# stm32f0_i2s.net
KiCad netlist of a schematic drawn in EAGLE
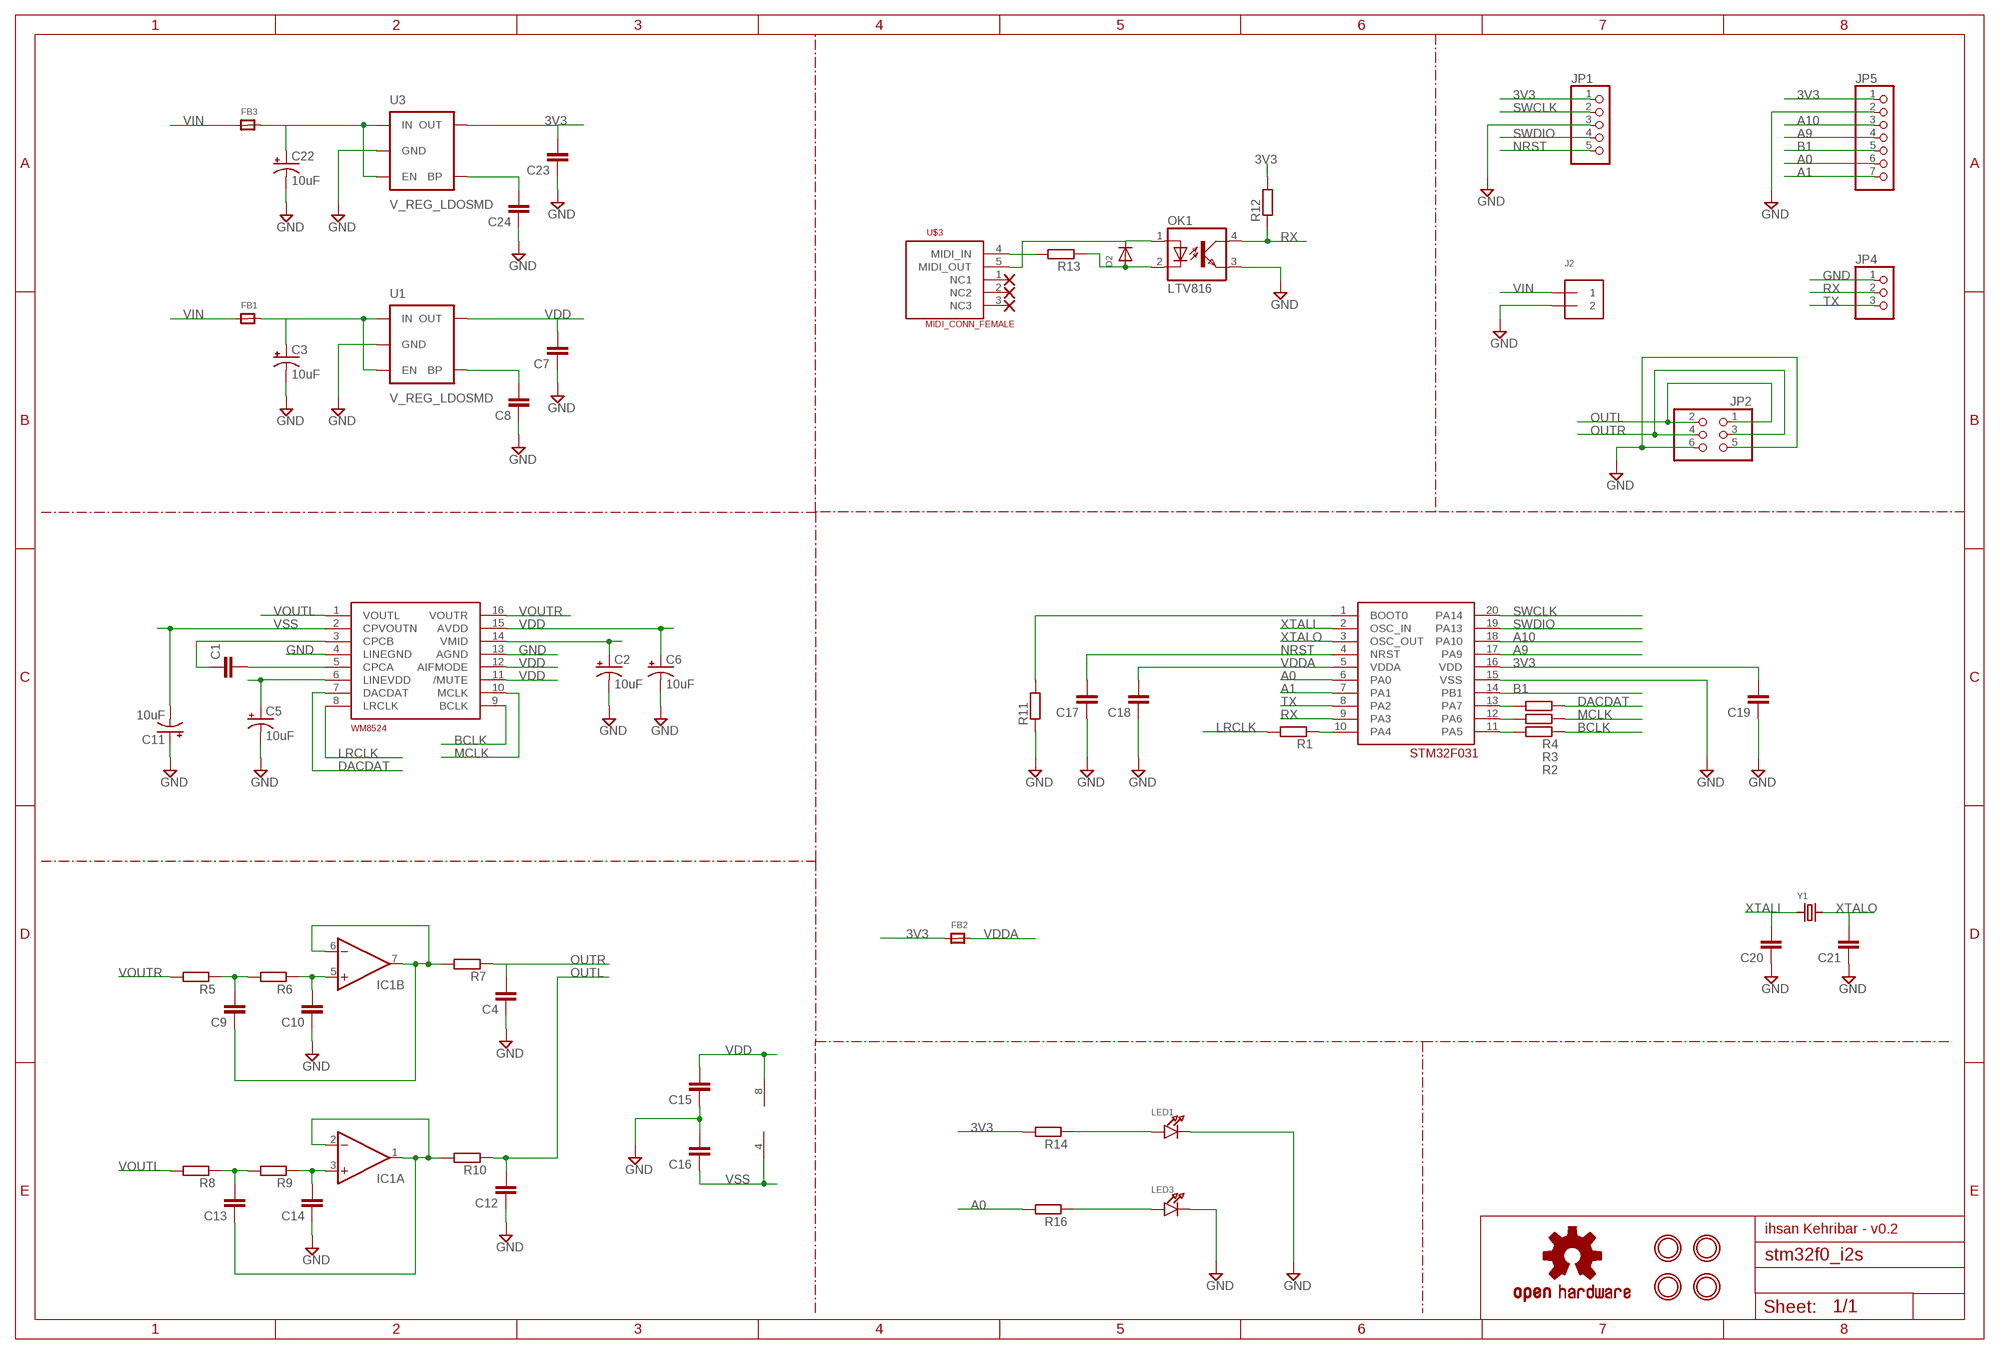
[diagram p0: schematic, sheet 1]

(export (version "E")
  (design (tool "Eeschema 10.0.6"))
  (components
    (comp (ref "C1")
      (value "C-EUC0805")
      (footprint "eagle-import:C0805")
      (libsource (lib "eagle-import") (part "C-EUC0805"))
    )
    (comp (ref "C2")
      (value "10uF")
      (footprint "eagle-import:EIA3216")
      (libsource (lib "eagle-import") (part "10UF-TANT"))
    )
    (comp (ref "C3")
      (value "10uF")
      (footprint "eagle-import:EIA3216")
      (libsource (lib "eagle-import") (part "10UF-TANT"))
    )
    (comp (ref "C4")
      (value "C-EUC0805")
      (footprint "eagle-import:C0805")
      (libsource (lib "eagle-import") (part "C-EUC0805"))
    )
    (comp (ref "C5")
      (value "10uF")
      (footprint "eagle-import:EIA3216")
      (libsource (lib "eagle-import") (part "10UF-TANT"))
    )
    (comp (ref "C6")
      (value "10uF")
      (footprint "eagle-import:EIA3216")
      (libsource (lib "eagle-import") (part "10UF-TANT"))
    )
    (comp (ref "C7")
      (value "C-EUC0805")
      (footprint "eagle-import:C0805")
      (libsource (lib "eagle-import") (part "C-EUC0805"))
    )
    (comp (ref "C8")
      (value "C-EUC0805")
      (footprint "eagle-import:C0805")
      (libsource (lib "eagle-import") (part "C-EUC0805"))
    )
    (comp (ref "C9")
      (value "C-EUC0805")
      (footprint "eagle-import:C0805")
      (libsource (lib "eagle-import") (part "C-EUC0805"))
    )
    (comp (ref "C10")
      (value "C-EUC0805")
      (footprint "eagle-import:C0805")
      (libsource (lib "eagle-import") (part "C-EUC0805"))
    )
    (comp (ref "C11")
      (value "10uF")
      (footprint "eagle-import:EIA3216")
      (libsource (lib "eagle-import") (part "10UF-TANT"))
    )
    (comp (ref "C12")
      (value "C-EUC0805")
      (footprint "eagle-import:C0805")
      (libsource (lib "eagle-import") (part "C-EUC0805"))
    )
    (comp (ref "C13")
      (value "C-EUC0805")
      (footprint "eagle-import:C0805")
      (libsource (lib "eagle-import") (part "C-EUC0805"))
    )
    (comp (ref "C14")
      (value "C-EUC0805")
      (footprint "eagle-import:C0805")
      (libsource (lib "eagle-import") (part "C-EUC0805"))
    )
    (comp (ref "C15")
      (value "C-EUC0805")
      (footprint "eagle-import:C0805")
      (libsource (lib "eagle-import") (part "C-EUC0805"))
    )
    (comp (ref "C16")
      (value "C-EUC0805")
      (footprint "eagle-import:C0805")
      (libsource (lib "eagle-import") (part "C-EUC0805"))
    )
    (comp (ref "C17")
      (value "C-EUC0805")
      (footprint "eagle-import:C0805")
      (libsource (lib "eagle-import") (part "C-EUC0805"))
    )
    (comp (ref "C18")
      (value "C-EUC0805")
      (footprint "eagle-import:C0805")
      (libsource (lib "eagle-import") (part "C-EUC0805"))
    )
    (comp (ref "C19")
      (value "C-EUC0805")
      (footprint "eagle-import:C0805")
      (libsource (lib "eagle-import") (part "C-EUC0805"))
    )
    (comp (ref "C20")
      (value "C-EUC0805")
      (footprint "eagle-import:C0805")
      (libsource (lib "eagle-import") (part "C-EUC0805"))
    )
    (comp (ref "C21")
      (value "C-EUC0805")
      (footprint "eagle-import:C0805")
      (libsource (lib "eagle-import") (part "C-EUC0805"))
    )
    (comp (ref "C22")
      (value "10uF")
      (footprint "eagle-import:EIA3216")
      (libsource (lib "eagle-import") (part "10UF-TANT"))
    )
    (comp (ref "C23")
      (value "C-EUC0805")
      (footprint "eagle-import:C0805")
      (libsource (lib "eagle-import") (part "C-EUC0805"))
    )
    (comp (ref "C24")
      (value "C-EUC0805")
      (footprint "eagle-import:C0805")
      (libsource (lib "eagle-import") (part "C-EUC0805"))
    )
    (comp (ref "D2")
      (value "DIODEDO-1N4148")
      (footprint "eagle-import:DO-1N4148")
      (libsource (lib "eagle-import") (part "DIODEDO-1N4148"))
    )
    (comp (ref "FB1")
      (value "FERRITE0805")
      (footprint "eagle-import:0805")
      (libsource (lib "eagle-import") (part "FERRITE0805"))
    )
    (comp (ref "FB2")
      (value "FERRITE0805")
      (footprint "eagle-import:0805")
      (libsource (lib "eagle-import") (part "FERRITE0805"))
    )
    (comp (ref "FB3")
      (value "FERRITE0805")
      (footprint "eagle-import:0805")
      (libsource (lib "eagle-import") (part "FERRITE0805"))
    )
    (comp (ref "IC1")
      (value "TL082D")
      (footprint "eagle-import:SO08")
      (libsource (lib "eagle-import") (part "TL082D"))
    )
    (comp (ref "J2")
      (value "TERMBLOCK_1X2")
      (footprint "eagle-import:TERMBLOCK_1X2-3.5MM")
      (libsource (lib "eagle-import") (part "TERMBLOCK_1X2"))
    )
    (comp (ref "JP1")
      (value "HEADER-1X5ROUND")
      (footprint "eagle-import:1X05_ROUND")
      (libsource (lib "eagle-import") (part "HEADER-1X5ROUND"))
    )
    (comp (ref "JP2")
      (value "PINHD-2X3")
      (footprint "eagle-import:2X03")
      (libsource (lib "eagle-import") (part "PINHD-2X3"))
    )
    (comp (ref "JP4")
      (value "HEADER-1X3ROUND")
      (footprint "eagle-import:1X03_ROUND")
      (libsource (lib "eagle-import") (part "HEADER-1X3ROUND"))
    )
    (comp (ref "JP5")
      (value "HEADER-1X7ROUND")
      (footprint "eagle-import:1X07_ROUND")
      (libsource (lib "eagle-import") (part "HEADER-1X7ROUND"))
    )
    (comp (ref "LED1")
      (value "LED1206")
      (footprint "eagle-import:CHIPLED_1206")
      (libsource (lib "eagle-import") (part "LED1206"))
    )
    (comp (ref "LED3")
      (value "LED1206")
      (footprint "eagle-import:CHIPLED_1206")
      (libsource (lib "eagle-import") (part "LED1206"))
    )
    (comp (ref "LOGO1")
      (value "OSHW-LOGOM")
      (footprint "eagle-import:OSHW-LOGO-M")
      (libsource (lib "eagle-import") (part "OSHW-LOGOM"))
    )
    (comp (ref "OK1")
      (value "LTV816")
      (footprint "eagle-import:DIL04")
      (libsource (lib "eagle-import") (part "LTV816"))
    )
    (comp (ref "R1")
      (value "R-EU_R0805")
      (footprint "eagle-import:R0805")
      (libsource (lib "eagle-import") (part "R-EU_R0805"))
    )
    (comp (ref "R2")
      (value "R-EU_R0805")
      (footprint "eagle-import:R0805")
      (libsource (lib "eagle-import") (part "R-EU_R0805"))
    )
    (comp (ref "R3")
      (value "R-EU_R0805")
      (footprint "eagle-import:R0805")
      (libsource (lib "eagle-import") (part "R-EU_R0805"))
    )
    (comp (ref "R4")
      (value "R-EU_R0805")
      (footprint "eagle-import:R0805")
      (libsource (lib "eagle-import") (part "R-EU_R0805"))
    )
    (comp (ref "R5")
      (value "R-EU_R0805")
      (footprint "eagle-import:R0805")
      (libsource (lib "eagle-import") (part "R-EU_R0805"))
    )
    (comp (ref "R6")
      (value "R-EU_R0805")
      (footprint "eagle-import:R0805")
      (libsource (lib "eagle-import") (part "R-EU_R0805"))
    )
    (comp (ref "R7")
      (value "R-EU_R0805")
      (footprint "eagle-import:R0805")
      (libsource (lib "eagle-import") (part "R-EU_R0805"))
    )
    (comp (ref "R8")
      (value "R-EU_R0805")
      (footprint "eagle-import:R0805")
      (libsource (lib "eagle-import") (part "R-EU_R0805"))
    )
    (comp (ref "R9")
      (value "R-EU_R0805")
      (footprint "eagle-import:R0805")
      (libsource (lib "eagle-import") (part "R-EU_R0805"))
    )
    (comp (ref "R10")
      (value "R-EU_R0805")
      (footprint "eagle-import:R0805")
      (libsource (lib "eagle-import") (part "R-EU_R0805"))
    )
    (comp (ref "R11")
      (value "R-EU_R0805")
      (footprint "eagle-import:R0805")
      (libsource (lib "eagle-import") (part "R-EU_R0805"))
    )
    (comp (ref "R12")
      (value "R-EU_R0805")
      (footprint "eagle-import:R0805")
      (libsource (lib "eagle-import") (part "R-EU_R0805"))
    )
    (comp (ref "R13")
      (value "R-EU_R0805")
      (footprint "eagle-import:R0805")
      (libsource (lib "eagle-import") (part "R-EU_R0805"))
    )
    (comp (ref "R14")
      (value "R-EU_R0805")
      (footprint "eagle-import:R0805")
      (libsource (lib "eagle-import") (part "R-EU_R0805"))
    )
    (comp (ref "R16")
      (value "R-EU_R0805")
      (footprint "eagle-import:R0805")
      (libsource (lib "eagle-import") (part "R-EU_R0805"))
    )
    (comp (ref "U$1")
      (value "IHSAN_WM8524")
      (footprint "eagle-import:TSSOP16")
      (libsource (lib "eagle-import") (part "IHSAN_WM8524"))
    )
    (comp (ref "U$2")
      (value "IHSAN_STM32F031")
      (footprint "eagle-import:TSSOP20")
      (libsource (lib "eagle-import") (part "IHSAN_STM32F031"))
    )
    (comp (ref "U$3")
      (value "MIDI_CONN_FEMALE")
      (footprint "eagle-import:DIN_5_FEMALE")
      (libsource (lib "eagle-import") (part "MIDI_CONN_FEMALE"))
    )
    (comp (ref "U$4")
      (value "MOUNTINGHOLE3.0THIN")
      (footprint "eagle-import:MOUNTINGHOLE_3.0_PLATEDTHIN")
      (libsource (lib "eagle-import") (part "MOUNTINGHOLE3.0THIN"))
    )
    (comp (ref "U$5")
      (value "MOUNTINGHOLE3.0THIN")
      (footprint "eagle-import:MOUNTINGHOLE_3.0_PLATEDTHIN")
      (libsource (lib "eagle-import") (part "MOUNTINGHOLE3.0THIN"))
    )
    (comp (ref "U$6")
      (value "MOUNTINGHOLE3.0THIN")
      (footprint "eagle-import:MOUNTINGHOLE_3.0_PLATEDTHIN")
      (libsource (lib "eagle-import") (part "MOUNTINGHOLE3.0THIN"))
    )
    (comp (ref "U$7")
      (value "MOUNTINGHOLE3.0THIN")
      (footprint "eagle-import:MOUNTINGHOLE_3.0_PLATEDTHIN")
      (libsource (lib "eagle-import") (part "MOUNTINGHOLE3.0THIN"))
    )
    (comp (ref "U1")
      (value "V_REG_LDOSMD")
      (footprint "eagle-import:SOT23-5")
      (libsource (lib "eagle-import") (part "V_REG_LDOSMD"))
    )
    (comp (ref "U3")
      (value "V_REG_LDOSMD")
      (footprint "eagle-import:SOT23-5")
      (libsource (lib "eagle-import") (part "V_REG_LDOSMD"))
    )
    (comp (ref "Y1")
      (value "CRYSTALTHIN32K")
      (footprint "eagle-import:CRYSTAL_4.9X1.8")
      (libsource (lib "eagle-import") (part "CRYSTALTHIN32K"))
    )
  )
  (nets
    (net (code "1") (name "/3V3") (class "Default")
      (node (ref "C19") (pin "2") (pinfunction "2_2") (pintype "passive"))
      (node (ref "C23") (pin "2") (pinfunction "2_2") (pintype "passive"))
      (node (ref "FB2") (pin "1") (pinfunction "P$1_1") (pintype "passive"))
      (node (ref "JP1") (pin "1") (pinfunction "1_1") (pintype "passive"))
      (node (ref "JP5") (pin "1") (pinfunction "1_1") (pintype "passive"))
      (node (ref "R12") (pin "2") (pinfunction "2_2") (pintype "passive"))
      (node (ref "R14") (pin "2") (pinfunction "2_2") (pintype "passive"))
      (node (ref "U$2") (pin "16") (pinfunction "VDD_16") (pintype "bidirectional"))
      (node (ref "U3") (pin "5") (pinfunction "OUT_5") (pintype "passive"))
    )
    (net (code "2") (name "/A0") (class "Default")
      (node (ref "JP5") (pin "6") (pinfunction "6_6") (pintype "passive"))
      (node (ref "R16") (pin "2") (pinfunction "2_2") (pintype "passive"))
      (node (ref "U$2") (pin "6") (pinfunction "PA0_6") (pintype "bidirectional"))
    )
    (net (code "3") (name "/A1") (class "Default")
      (node (ref "JP5") (pin "7") (pinfunction "7_7") (pintype "passive"))
      (node (ref "U$2") (pin "7") (pinfunction "PA1_7") (pintype "bidirectional"))
    )
    (net (code "4") (name "/A9") (class "Default")
      (node (ref "JP5") (pin "4") (pinfunction "4_4") (pintype "passive"))
      (node (ref "U$2") (pin "17") (pinfunction "PA9_17") (pintype "bidirectional"))
    )
    (net (code "5") (name "/A10") (class "Default")
      (node (ref "JP5") (pin "3") (pinfunction "3_3") (pintype "passive"))
      (node (ref "U$2") (pin "18") (pinfunction "PA10_18") (pintype "bidirectional"))
    )
    (net (code "6") (name "/B1") (class "Default")
      (node (ref "JP5") (pin "5") (pinfunction "5_5") (pintype "passive"))
      (node (ref "U$2") (pin "14") (pinfunction "PB1_14") (pintype "bidirectional"))
    )
    (net (code "7") (name "/BCLK") (class "Default")
      (node (ref "R2") (pin "1") (pinfunction "1_1") (pintype "passive"))
      (node (ref "U$1") (pin "9") (pinfunction "BCLK_9") (pintype "bidirectional"))
    )
    (net (code "8") (name "/DACDAT") (class "Default")
      (node (ref "R4") (pin "1") (pinfunction "1_1") (pintype "passive"))
      (node (ref "U$1") (pin "7") (pinfunction "DACDAT_7") (pintype "bidirectional"))
    )
    (net (code "9") (name "/LRCLK") (class "Default")
      (node (ref "R1") (pin "2") (pinfunction "2_2") (pintype "passive"))
      (node (ref "U$1") (pin "8") (pinfunction "LRCLK_8") (pintype "bidirectional"))
    )
    (net (code "10") (name "/MCLK") (class "Default")
      (node (ref "R3") (pin "1") (pinfunction "1_1") (pintype "passive"))
      (node (ref "U$1") (pin "10") (pinfunction "MCLK_10") (pintype "bidirectional"))
    )
    (net (code "11") (name "/NRST") (class "Default")
      (node (ref "C17") (pin "2") (pinfunction "2_2") (pintype "passive"))
      (node (ref "JP1") (pin "5") (pinfunction "5_5") (pintype "passive"))
      (node (ref "U$2") (pin "4") (pinfunction "NRST_4") (pintype "bidirectional"))
    )
    (net (code "12") (name "/OUTL") (class "Default")
      (node (ref "C12") (pin "2") (pinfunction "2_2") (pintype "passive"))
      (node (ref "JP2") (pin "1") (pinfunction "1_1") (pintype "passive"))
      (node (ref "JP2") (pin "2") (pinfunction "2_2") (pintype "passive"))
      (node (ref "R10") (pin "1") (pinfunction "1_1") (pintype "passive"))
    )
    (net (code "13") (name "/OUTR") (class "Default")
      (node (ref "C4") (pin "2") (pinfunction "2_2") (pintype "passive"))
      (node (ref "JP2") (pin "3") (pinfunction "3_3") (pintype "passive"))
      (node (ref "JP2") (pin "4") (pinfunction "4_4") (pintype "passive"))
      (node (ref "R7") (pin "1") (pinfunction "1_1") (pintype "passive"))
    )
    (net (code "14") (name "/RX") (class "Default")
      (node (ref "JP4") (pin "2") (pinfunction "2_2") (pintype "passive"))
      (node (ref "OK1") (pin "4") (pinfunction "COL_4") (pintype "passive"))
      (node (ref "R12") (pin "1") (pinfunction "1_1") (pintype "passive"))
      (node (ref "U$2") (pin "9") (pinfunction "PA3_9") (pintype "bidirectional"))
    )
    (net (code "15") (name "/SWCLK") (class "Default")
      (node (ref "JP1") (pin "2") (pinfunction "2_2") (pintype "passive"))
      (node (ref "U$2") (pin "20") (pinfunction "PA14_20") (pintype "bidirectional"))
    )
    (net (code "16") (name "/SWDIO") (class "Default")
      (node (ref "JP1") (pin "4") (pinfunction "4_4") (pintype "passive"))
      (node (ref "U$2") (pin "19") (pinfunction "PA13_19") (pintype "bidirectional"))
    )
    (net (code "17") (name "/TX") (class "Default")
      (node (ref "JP4") (pin "3") (pinfunction "3_3") (pintype "passive"))
      (node (ref "U$2") (pin "8") (pinfunction "PA2_8") (pintype "bidirectional"))
    )
    (net (code "18") (name "/VDD") (class "Default")
      (node (ref "C15") (pin "2") (pinfunction "2_2") (pintype "passive"))
      (node (ref "C6") (pin "A") (pinfunction "+_A") (pintype "passive"))
      (node (ref "C7") (pin "2") (pinfunction "2_2") (pintype "passive"))
      (node (ref "IC1") (pin "8") (pinfunction "V+_8") (pintype "power_in"))
      (node (ref "U$1") (pin "11") (pinfunction "/MUTE_11") (pintype "bidirectional"))
      (node (ref "U$1") (pin "12") (pinfunction "AIFMODE_12") (pintype "bidirectional"))
      (node (ref "U$1") (pin "15") (pinfunction "AVDD_15") (pintype "bidirectional"))
      (node (ref "U1") (pin "5") (pinfunction "OUT_5") (pintype "passive"))
    )
    (net (code "19") (name "/VDDA") (class "Default")
      (node (ref "C18") (pin "2") (pinfunction "2_2") (pintype "passive"))
      (node (ref "FB2") (pin "2") (pinfunction "P$2_2") (pintype "passive"))
      (node (ref "U$2") (pin "5") (pinfunction "VDDA_5") (pintype "bidirectional"))
    )
    (net (code "20") (name "/VIN") (class "Default")
      (node (ref "FB1") (pin "1") (pinfunction "P$1_1") (pintype "passive"))
      (node (ref "FB3") (pin "1") (pinfunction "P$1_1") (pintype "passive"))
      (node (ref "J2") (pin "1") (pinfunction "1_1") (pintype "passive"))
    )
    (net (code "21") (name "/VOUTL") (class "Default")
      (node (ref "R8") (pin "2") (pinfunction "2_2") (pintype "passive"))
      (node (ref "U$1") (pin "1") (pinfunction "VOUTL_1") (pintype "bidirectional"))
    )
    (net (code "22") (name "/VOUTR") (class "Default")
      (node (ref "R5") (pin "2") (pinfunction "2_2") (pintype "passive"))
      (node (ref "U$1") (pin "16") (pinfunction "VOUTR_16") (pintype "bidirectional"))
    )
    (net (code "23") (name "/VSS") (class "Default")
      (node (ref "C11") (pin "C") (pinfunction "-_C") (pintype "passive"))
      (node (ref "C16") (pin "1") (pinfunction "1_1") (pintype "passive"))
      (node (ref "IC1") (pin "4") (pinfunction "V-_4") (pintype "power_in"))
      (node (ref "U$1") (pin "2") (pinfunction "CPVOUTN_2") (pintype "bidirectional"))
    )
    (net (code "24") (name "/XTALI") (class "Default")
      (node (ref "C20") (pin "2") (pinfunction "2_2") (pintype "passive"))
      (node (ref "U$2") (pin "2") (pinfunction "OSC_IN_2") (pintype "bidirectional"))
      (node (ref "Y1") (pin "1") (pinfunction "1_1") (pintype "passive"))
    )
    (net (code "25") (name "/XTALO") (class "Default")
      (node (ref "C21") (pin "2") (pinfunction "2_2") (pintype "passive"))
      (node (ref "U$2") (pin "3") (pinfunction "OSC_OUT_3") (pintype "bidirectional"))
      (node (ref "Y1") (pin "2") (pinfunction "2_2") (pintype "passive"))
    )
    (net (code "26") (name "GND") (class "Default")
      (node (ref "C10") (pin "1") (pinfunction "1_1") (pintype "passive"))
      (node (ref "C11") (pin "A") (pinfunction "+_A") (pintype "passive"))
      (node (ref "C12") (pin "1") (pinfunction "1_1") (pintype "passive"))
      (node (ref "C14") (pin "1") (pinfunction "1_1") (pintype "passive"))
      (node (ref "C15") (pin "1") (pinfunction "1_1") (pintype "passive"))
      (node (ref "C16") (pin "2") (pinfunction "2_2") (pintype "passive"))
      (node (ref "C17") (pin "1") (pinfunction "1_1") (pintype "passive"))
      (node (ref "C18") (pin "1") (pinfunction "1_1") (pintype "passive"))
      (node (ref "C19") (pin "1") (pinfunction "1_1") (pintype "passive"))
      (node (ref "C2") (pin "C") (pinfunction "-_C") (pintype "passive"))
      (node (ref "C20") (pin "1") (pinfunction "1_1") (pintype "passive"))
      (node (ref "C21") (pin "1") (pinfunction "1_1") (pintype "passive"))
      (node (ref "C22") (pin "C") (pinfunction "-_C") (pintype "passive"))
      (node (ref "C23") (pin "1") (pinfunction "1_1") (pintype "passive"))
      (node (ref "C24") (pin "1") (pinfunction "1_1") (pintype "passive"))
      (node (ref "C3") (pin "C") (pinfunction "-_C") (pintype "passive"))
      (node (ref "C4") (pin "1") (pinfunction "1_1") (pintype "passive"))
      (node (ref "C5") (pin "C") (pinfunction "-_C") (pintype "passive"))
      (node (ref "C6") (pin "C") (pinfunction "-_C") (pintype "passive"))
      (node (ref "C7") (pin "1") (pinfunction "1_1") (pintype "passive"))
      (node (ref "C8") (pin "1") (pinfunction "1_1") (pintype "passive"))
      (node (ref "J2") (pin "2") (pinfunction "2_2") (pintype "passive"))
      (node (ref "JP1") (pin "3") (pinfunction "3_3") (pintype "passive"))
      (node (ref "JP2") (pin "5") (pinfunction "5_5") (pintype "passive"))
      (node (ref "JP2") (pin "6") (pinfunction "6_6") (pintype "passive"))
      (node (ref "JP4") (pin "1") (pinfunction "1_1") (pintype "passive"))
      (node (ref "JP5") (pin "2") (pinfunction "2_2") (pintype "passive"))
      (node (ref "LED1") (pin "C") (pinfunction "C_C") (pintype "passive"))
      (node (ref "LED3") (pin "C") (pinfunction "C_C") (pintype "passive"))
      (node (ref "OK1") (pin "3") (pinfunction "EMIT_3") (pintype "passive"))
      (node (ref "R11") (pin "1") (pinfunction "1_1") (pintype "passive"))
      (node (ref "U$1") (pin "13") (pinfunction "AGND_13") (pintype "bidirectional"))
      (node (ref "U$1") (pin "4") (pinfunction "LINEGND_4") (pintype "bidirectional"))
      (node (ref "U$2") (pin "15") (pinfunction "VSS_15") (pintype "bidirectional"))
      (node (ref "U1") (pin "2") (pinfunction "GND_2") (pintype "input"))
      (node (ref "U3") (pin "2") (pinfunction "GND_2") (pintype "input"))
    )
    (net (code "27") (name "Net-(C2-+)") (class "Default")
      (node (ref "C2") (pin "A") (pinfunction "+_A") (pintype "passive"))
      (node (ref "U$1") (pin "14") (pinfunction "VMID_14") (pintype "bidirectional"))
    )
    (net (code "28") (name "Net-(C3-+)") (class "Default")
      (node (ref "C3") (pin "A") (pinfunction "+_A") (pintype "passive"))
      (node (ref "FB1") (pin "2") (pinfunction "P$2_2") (pintype "passive"))
      (node (ref "U1") (pin "1") (pinfunction "IN_1") (pintype "input"))
      (node (ref "U1") (pin "3") (pinfunction "EN_3") (pintype "input"))
    )
    (net (code "29") (name "Net-(C5-+)") (class "Default")
      (node (ref "C5") (pin "A") (pinfunction "+_A") (pintype "passive"))
      (node (ref "U$1") (pin "6") (pinfunction "LINEVDD_6") (pintype "bidirectional"))
    )
    (net (code "30") (name "Net-(C9-Pad2)") (class "Default")
      (node (ref "C9") (pin "2") (pinfunction "2_2") (pintype "passive"))
      (node (ref "R5") (pin "1") (pinfunction "1_1") (pintype "passive"))
      (node (ref "R6") (pin "2") (pinfunction "2_2") (pintype "passive"))
    )
    (net (code "31") (name "Net-(C13-Pad2)") (class "Default")
      (node (ref "C13") (pin "2") (pinfunction "2_2") (pintype "passive"))
      (node (ref "R8") (pin "1") (pinfunction "1_1") (pintype "passive"))
      (node (ref "R9") (pin "2") (pinfunction "2_2") (pintype "passive"))
    )
    (net (code "32") (name "Net-(C22-+)") (class "Default")
      (node (ref "C22") (pin "A") (pinfunction "+_A") (pintype "passive"))
      (node (ref "FB3") (pin "2") (pinfunction "P$2_2") (pintype "passive"))
      (node (ref "U3") (pin "1") (pinfunction "IN_1") (pintype "input"))
      (node (ref "U3") (pin "3") (pinfunction "EN_3") (pintype "input"))
    )
    (net (code "33") (name "Net-(IC1A-+IN)") (class "Default")
      (node (ref "C14") (pin "2") (pinfunction "2_2") (pintype "passive"))
      (node (ref "IC1") (pin "3") (pinfunction "+IN_3") (pintype "input"))
      (node (ref "R9") (pin "1") (pinfunction "1_1") (pintype "passive"))
    )
    (net (code "34") (name "Net-(IC1A--IN)") (class "Default")
      (node (ref "C13") (pin "1") (pinfunction "1_1") (pintype "passive"))
      (node (ref "IC1") (pin "1") (pinfunction "OUT_1") (pintype "output"))
      (node (ref "IC1") (pin "2") (pinfunction "-IN_2") (pintype "input"))
      (node (ref "R10") (pin "2") (pinfunction "2_2") (pintype "passive"))
    )
    (net (code "35") (name "Net-(IC1B-+IN)") (class "Default")
      (node (ref "C10") (pin "2") (pinfunction "2_2") (pintype "passive"))
      (node (ref "IC1") (pin "5") (pinfunction "+IN_5") (pintype "input"))
      (node (ref "R6") (pin "1") (pinfunction "1_1") (pintype "passive"))
    )
    (net (code "36") (name "Net-(IC1B--IN)") (class "Default")
      (node (ref "C9") (pin "1") (pinfunction "1_1") (pintype "passive"))
      (node (ref "IC1") (pin "6") (pinfunction "-IN_6") (pintype "input"))
      (node (ref "IC1") (pin "7") (pinfunction "OUT_7") (pintype "output"))
      (node (ref "R7") (pin "2") (pinfunction "2_2") (pintype "passive"))
    )
    (net (code "37") (name "Net-(LED1-PadA)") (class "Default")
      (node (ref "LED1") (pin "A") (pinfunction "A_A") (pintype "passive"))
      (node (ref "R14") (pin "1") (pinfunction "1_1") (pintype "passive"))
    )
    (net (code "38") (name "Net-(LED3-PadA)") (class "Default")
      (node (ref "LED3") (pin "A") (pinfunction "A_A") (pintype "passive"))
      (node (ref "R16") (pin "1") (pinfunction "1_1") (pintype "passive"))
    )
    (net (code "39") (name "Net-(OK1-A)") (class "Default")
      (node (ref "D2") (pin "C") (pinfunction "C_C") (pintype "passive"))
      (node (ref "OK1") (pin "1") (pinfunction "A_1") (pintype "passive"))
      (node (ref "U$3") (pin "5") (pinfunction "MIDI_OUT_5") (pintype "bidirectional"))
    )
    (net (code "40") (name "Net-(OK1-C)") (class "Default")
      (node (ref "D2") (pin "A") (pinfunction "A_A") (pintype "passive"))
      (node (ref "OK1") (pin "2") (pinfunction "C_2") (pintype "passive"))
      (node (ref "R13") (pin "1") (pinfunction "1_1") (pintype "passive"))
    )
    (net (code "41") (name "Net-(U$1-CPCA)") (class "Default")
      (node (ref "C1") (pin "2") (pinfunction "2_2") (pintype "passive"))
      (node (ref "U$1") (pin "5") (pinfunction "CPCA_5") (pintype "bidirectional"))
    )
    (net (code "42") (name "Net-(U$1-CPCB)") (class "Default")
      (node (ref "C1") (pin "1") (pinfunction "1_1") (pintype "passive"))
      (node (ref "U$1") (pin "3") (pinfunction "CPCB_3") (pintype "bidirectional"))
    )
    (net (code "43") (name "Net-(U$2-BOOT0)") (class "Default")
      (node (ref "R11") (pin "2") (pinfunction "2_2") (pintype "passive"))
      (node (ref "U$2") (pin "1") (pinfunction "BOOT0_1") (pintype "bidirectional"))
    )
    (net (code "44") (name "Net-(U$2-PA4)") (class "Default")
      (node (ref "R1") (pin "1") (pinfunction "1_1") (pintype "passive"))
      (node (ref "U$2") (pin "10") (pinfunction "PA4_10") (pintype "bidirectional"))
    )
    (net (code "45") (name "Net-(U$2-PA5)") (class "Default")
      (node (ref "R2") (pin "2") (pinfunction "2_2") (pintype "passive"))
      (node (ref "U$2") (pin "11") (pinfunction "PA5_11") (pintype "bidirectional"))
    )
    (net (code "46") (name "Net-(U$2-PA6)") (class "Default")
      (node (ref "R3") (pin "2") (pinfunction "2_2") (pintype "passive"))
      (node (ref "U$2") (pin "12") (pinfunction "PA6_12") (pintype "bidirectional"))
    )
    (net (code "47") (name "Net-(U$2-PA7)") (class "Default")
      (node (ref "R4") (pin "2") (pinfunction "2_2") (pintype "passive"))
      (node (ref "U$2") (pin "13") (pinfunction "PA7_13") (pintype "bidirectional"))
    )
    (net (code "48") (name "Net-(U$3-MIDI_IN)") (class "Default")
      (node (ref "R13") (pin "2") (pinfunction "2_2") (pintype "passive"))
      (node (ref "U$3") (pin "4") (pinfunction "MIDI_IN_4") (pintype "bidirectional"))
    )
    (net (code "49") (name "Net-(U1-BP)") (class "Default")
      (node (ref "C8") (pin "2") (pinfunction "2_2") (pintype "passive"))
      (node (ref "U1") (pin "4") (pinfunction "BP_4") (pintype "input"))
    )
    (net (code "50") (name "Net-(U3-BP)") (class "Default")
      (node (ref "C24") (pin "2") (pinfunction "2_2") (pintype "passive"))
      (node (ref "U3") (pin "4") (pinfunction "BP_4") (pintype "input"))
    )
    (net (code "51") (name "unconnected-(U$3-NC1-Pad1)") (class "Default")
      (node (ref "U$3") (pin "1") (pinfunction "NC1_1") (pintype "bidirectional"))
    )
    (net (code "52") (name "unconnected-(U$3-NC2-Pad2)") (class "Default")
      (node (ref "U$3") (pin "2") (pinfunction "NC2_2") (pintype "bidirectional"))
    )
    (net (code "53") (name "unconnected-(U$3-NC3-Pad3)") (class "Default")
      (node (ref "U$3") (pin "3") (pinfunction "NC3_3") (pintype "bidirectional"))
    )
  )
)
